# G22V2.net
KiCad netlist of a schematic drawn in EAGLE
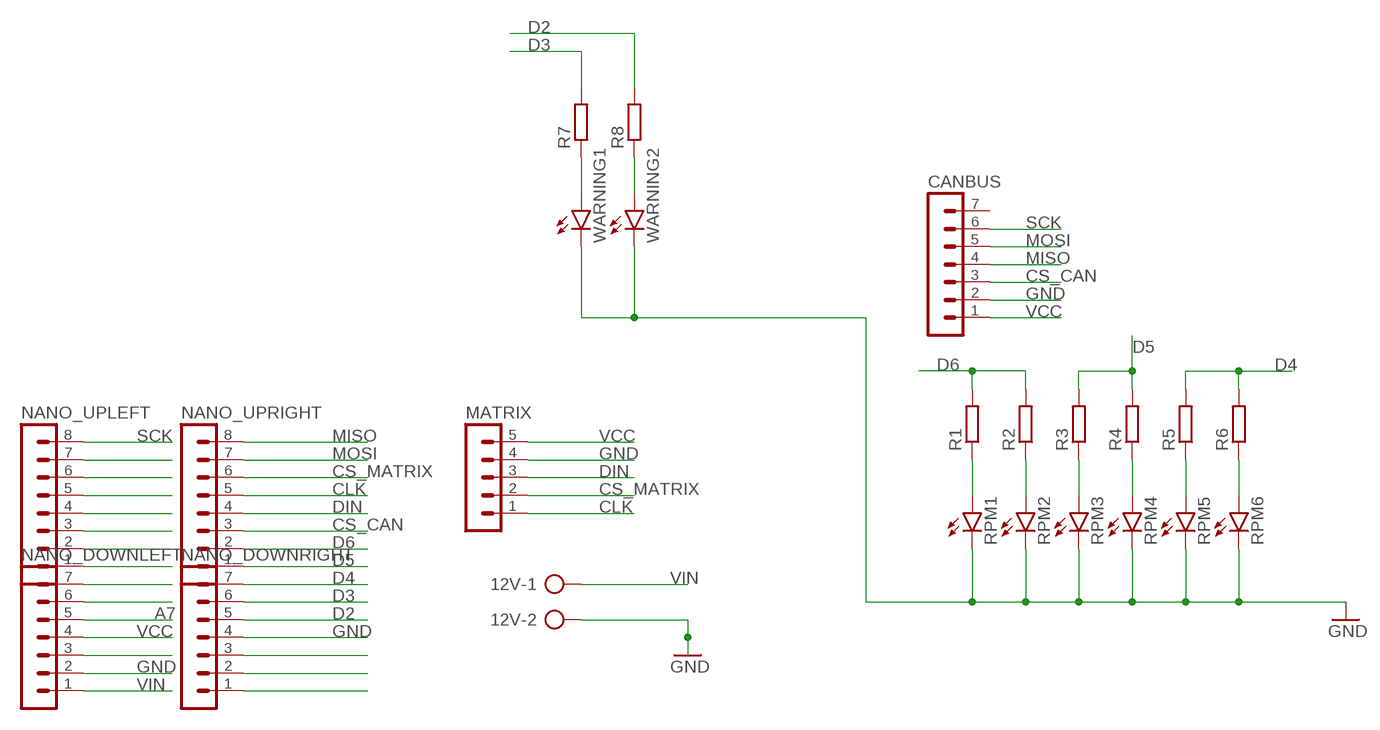
[diagram p0: schematic, sheet 1]

(export (version "E")
  (design (tool "Eeschema 10.0.6"))
  (components
    (comp (ref "12V")
      (value "AK500/2-H")
      (footprint "eagle-import:AK500_2-H")
      (libsource (lib "eagle-import") (part "AK500/2-H"))
    )
    (comp (ref "CANBUS")
      (value "MA07-1")
      (footprint "eagle-import:MA07-1")
      (libsource (lib "eagle-import") (part "MA07-1"))
    )
    (comp (ref "MATRIX")
      (value "MA05-1")
      (footprint "eagle-import:MA05-1")
      (libsource (lib "eagle-import") (part "MA05-1"))
    )
    (comp (ref "NANO_DOWNLEFT")
      (value "MA07-1")
      (footprint "eagle-import:MA07-1")
      (libsource (lib "eagle-import") (part "MA07-1"))
    )
    (comp (ref "NANO_DOWNRIGHT")
      (value "MA07-1")
      (footprint "eagle-import:MA07-1")
      (libsource (lib "eagle-import") (part "MA07-1"))
    )
    (comp (ref "NANO_UPLEFT")
      (value "MA08-1")
      (footprint "eagle-import:MA08-1")
      (libsource (lib "eagle-import") (part "MA08-1"))
    )
    (comp (ref "NANO_UPRIGHT")
      (value "MA08-1")
      (footprint "eagle-import:MA08-1")
      (libsource (lib "eagle-import") (part "MA08-1"))
    )
    (comp (ref "R1")
      (value "R-EU_0204/7")
      (footprint "eagle-import:0204_7")
      (libsource (lib "eagle-import") (part "R-EU_0204/7"))
    )
    (comp (ref "R2")
      (value "R-EU_0204/7")
      (footprint "eagle-import:0204_7")
      (libsource (lib "eagle-import") (part "R-EU_0204/7"))
    )
    (comp (ref "R3")
      (value "R-EU_0204/7")
      (footprint "eagle-import:0204_7")
      (libsource (lib "eagle-import") (part "R-EU_0204/7"))
    )
    (comp (ref "R4")
      (value "R-EU_0204/7")
      (footprint "eagle-import:0204_7")
      (libsource (lib "eagle-import") (part "R-EU_0204/7"))
    )
    (comp (ref "R5")
      (value "R-EU_0204/7")
      (footprint "eagle-import:0204_7")
      (libsource (lib "eagle-import") (part "R-EU_0204/7"))
    )
    (comp (ref "R6")
      (value "R-EU_0204/7")
      (footprint "eagle-import:0204_7")
      (libsource (lib "eagle-import") (part "R-EU_0204/7"))
    )
    (comp (ref "R7")
      (value "R-EU_0204/7")
      (footprint "eagle-import:0204_7")
      (libsource (lib "eagle-import") (part "R-EU_0204/7"))
    )
    (comp (ref "R8")
      (value "R-EU_0204/7")
      (footprint "eagle-import:0204_7")
      (libsource (lib "eagle-import") (part "R-EU_0204/7"))
    )
    (comp (ref "RPM1")
      (value "LED5MM")
      (footprint "eagle-import:LED5MM")
      (libsource (lib "eagle-import") (part "LED5MM"))
    )
    (comp (ref "RPM2")
      (value "LED5MM")
      (footprint "eagle-import:LED5MM")
      (libsource (lib "eagle-import") (part "LED5MM"))
    )
    (comp (ref "RPM3")
      (value "LED5MM")
      (footprint "eagle-import:LED5MM")
      (libsource (lib "eagle-import") (part "LED5MM"))
    )
    (comp (ref "RPM4")
      (value "LED5MM")
      (footprint "eagle-import:LED5MM")
      (libsource (lib "eagle-import") (part "LED5MM"))
    )
    (comp (ref "RPM5")
      (value "LED5MM")
      (footprint "eagle-import:LED5MM")
      (libsource (lib "eagle-import") (part "LED5MM"))
    )
    (comp (ref "RPM6")
      (value "LED5MM")
      (footprint "eagle-import:LED5MM")
      (libsource (lib "eagle-import") (part "LED5MM"))
    )
    (comp (ref "WARNING1")
      (value "LED5MM")
      (footprint "eagle-import:LED5MM")
      (libsource (lib "eagle-import") (part "LED5MM"))
    )
    (comp (ref "WARNING2")
      (value "LED5MM")
      (footprint "eagle-import:LED5MM")
      (libsource (lib "eagle-import") (part "LED5MM"))
    )
  )
  (nets
    (net (code "1") (name "/A7") (class "Default")
      (node (ref "NANO_DOWNLEFT") (pin "5") (pinfunction "5_5") (pintype "passive"))
    )
    (net (code "2") (name "/CLK") (class "Default")
      (node (ref "MATRIX") (pin "1") (pinfunction "1_1") (pintype "passive"))
      (node (ref "NANO_UPRIGHT") (pin "5") (pinfunction "5_5") (pintype "passive"))
    )
    (net (code "3") (name "/CS_CAN") (class "Default")
      (node (ref "CANBUS") (pin "3") (pinfunction "3_3") (pintype "passive"))
      (node (ref "NANO_UPRIGHT") (pin "3") (pinfunction "3_3") (pintype "passive"))
    )
    (net (code "4") (name "/CS_MATRIX") (class "Default")
      (node (ref "MATRIX") (pin "2") (pinfunction "2_2") (pintype "passive"))
      (node (ref "NANO_UPRIGHT") (pin "6") (pinfunction "6_6") (pintype "passive"))
    )
    (net (code "5") (name "/D2") (class "Default")
      (node (ref "NANO_DOWNRIGHT") (pin "5") (pinfunction "5_5") (pintype "passive"))
      (node (ref "R8") (pin "2") (pinfunction "2_2") (pintype "passive"))
    )
    (net (code "6") (name "/D3") (class "Default")
      (node (ref "NANO_DOWNRIGHT") (pin "6") (pinfunction "6_6") (pintype "passive"))
      (node (ref "R7") (pin "2") (pinfunction "2_2") (pintype "passive"))
    )
    (net (code "7") (name "/D4") (class "Default")
      (node (ref "NANO_DOWNRIGHT") (pin "7") (pinfunction "7_7") (pintype "passive"))
      (node (ref "R5") (pin "2") (pinfunction "2_2") (pintype "passive"))
      (node (ref "R6") (pin "2") (pinfunction "2_2") (pintype "passive"))
    )
    (net (code "8") (name "/D5") (class "Default")
      (node (ref "NANO_UPRIGHT") (pin "1") (pinfunction "1_1") (pintype "passive"))
      (node (ref "R3") (pin "2") (pinfunction "2_2") (pintype "passive"))
      (node (ref "R4") (pin "2") (pinfunction "2_2") (pintype "passive"))
    )
    (net (code "9") (name "/D6") (class "Default")
      (node (ref "NANO_UPRIGHT") (pin "2") (pinfunction "2_2") (pintype "passive"))
      (node (ref "R1") (pin "2") (pinfunction "2_2") (pintype "passive"))
      (node (ref "R2") (pin "2") (pinfunction "2_2") (pintype "passive"))
    )
    (net (code "10") (name "/DIN") (class "Default")
      (node (ref "MATRIX") (pin "3") (pinfunction "3_3") (pintype "passive"))
      (node (ref "NANO_UPRIGHT") (pin "4") (pinfunction "4_4") (pintype "passive"))
    )
    (net (code "11") (name "/MISO") (class "Default")
      (node (ref "CANBUS") (pin "4") (pinfunction "4_4") (pintype "passive"))
      (node (ref "NANO_UPRIGHT") (pin "8") (pinfunction "8_8") (pintype "passive"))
    )
    (net (code "12") (name "/MOSI") (class "Default")
      (node (ref "CANBUS") (pin "5") (pinfunction "5_5") (pintype "passive"))
      (node (ref "NANO_UPRIGHT") (pin "7") (pinfunction "7_7") (pintype "passive"))
    )
    (net (code "13") (name "/SCK") (class "Default")
      (node (ref "CANBUS") (pin "6") (pinfunction "6_6") (pintype "passive"))
      (node (ref "NANO_UPLEFT") (pin "8") (pinfunction "8_8") (pintype "passive"))
    )
    (net (code "14") (name "/VCC") (class "Default")
      (node (ref "CANBUS") (pin "1") (pinfunction "1_1") (pintype "passive"))
      (node (ref "MATRIX") (pin "5") (pinfunction "5_5") (pintype "passive"))
      (node (ref "NANO_DOWNLEFT") (pin "4") (pinfunction "4_4") (pintype "passive"))
    )
    (net (code "15") (name "/VIN") (class "Default")
      (node (ref "12V") (pin "1") (pinfunction "KL_1") (pintype "passive"))
      (node (ref "NANO_DOWNLEFT") (pin "1") (pinfunction "1_1") (pintype "passive"))
    )
    (net (code "16") (name "GND") (class "Default")
      (node (ref "12V") (pin "2") (pinfunction "KL_2") (pintype "passive"))
      (node (ref "CANBUS") (pin "2") (pinfunction "2_2") (pintype "passive"))
      (node (ref "MATRIX") (pin "4") (pinfunction "4_4") (pintype "passive"))
      (node (ref "NANO_DOWNLEFT") (pin "2") (pinfunction "2_2") (pintype "passive"))
      (node (ref "NANO_DOWNRIGHT") (pin "4") (pinfunction "4_4") (pintype "passive"))
      (node (ref "RPM1") (pin "K") (pinfunction "C_K") (pintype "passive"))
      (node (ref "RPM2") (pin "K") (pinfunction "C_K") (pintype "passive"))
      (node (ref "RPM3") (pin "K") (pinfunction "C_K") (pintype "passive"))
      (node (ref "RPM4") (pin "K") (pinfunction "C_K") (pintype "passive"))
      (node (ref "RPM5") (pin "K") (pinfunction "C_K") (pintype "passive"))
      (node (ref "RPM6") (pin "K") (pinfunction "C_K") (pintype "passive"))
      (node (ref "WARNING1") (pin "K") (pinfunction "C_K") (pintype "passive"))
      (node (ref "WARNING2") (pin "K") (pinfunction "C_K") (pintype "passive"))
    )
    (net (code "17") (name "Net-(R1-Pad1)") (class "Default")
      (node (ref "R1") (pin "1") (pinfunction "1_1") (pintype "passive"))
      (node (ref "RPM1") (pin "A") (pinfunction "A_A") (pintype "passive"))
    )
    (net (code "18") (name "Net-(R2-Pad1)") (class "Default")
      (node (ref "R2") (pin "1") (pinfunction "1_1") (pintype "passive"))
      (node (ref "RPM2") (pin "A") (pinfunction "A_A") (pintype "passive"))
    )
    (net (code "19") (name "Net-(R3-Pad1)") (class "Default")
      (node (ref "R3") (pin "1") (pinfunction "1_1") (pintype "passive"))
      (node (ref "RPM3") (pin "A") (pinfunction "A_A") (pintype "passive"))
    )
    (net (code "20") (name "Net-(R4-Pad1)") (class "Default")
      (node (ref "R4") (pin "1") (pinfunction "1_1") (pintype "passive"))
      (node (ref "RPM4") (pin "A") (pinfunction "A_A") (pintype "passive"))
    )
    (net (code "21") (name "Net-(R5-Pad1)") (class "Default")
      (node (ref "R5") (pin "1") (pinfunction "1_1") (pintype "passive"))
      (node (ref "RPM5") (pin "A") (pinfunction "A_A") (pintype "passive"))
    )
    (net (code "22") (name "Net-(R6-Pad1)") (class "Default")
      (node (ref "R6") (pin "1") (pinfunction "1_1") (pintype "passive"))
      (node (ref "RPM6") (pin "A") (pinfunction "A_A") (pintype "passive"))
    )
    (net (code "23") (name "Net-(R7-Pad1)") (class "Default")
      (node (ref "R7") (pin "1") (pinfunction "1_1") (pintype "passive"))
      (node (ref "WARNING1") (pin "A") (pinfunction "A_A") (pintype "passive"))
    )
    (net (code "24") (name "Net-(R8-Pad1)") (class "Default")
      (node (ref "R8") (pin "1") (pinfunction "1_1") (pintype "passive"))
      (node (ref "WARNING2") (pin "A") (pinfunction "A_A") (pintype "passive"))
    )
    (net (code "25") (name "unconnected-(CANBUS-Pad7)") (class "Default")
      (node (ref "CANBUS") (pin "7") (pinfunction "7_7") (pintype "passive"))
    )
    (net (code "26") (name "unconnected-(NANO_DOWNLEFT-Pad3)") (class "Default")
      (node (ref "NANO_DOWNLEFT") (pin "3") (pinfunction "3_3") (pintype "passive"))
    )
    (net (code "27") (name "unconnected-(NANO_DOWNLEFT-Pad6)") (class "Default")
      (node (ref "NANO_DOWNLEFT") (pin "6") (pinfunction "6_6") (pintype "passive"))
    )
    (net (code "28") (name "unconnected-(NANO_DOWNLEFT-Pad7)") (class "Default")
      (node (ref "NANO_DOWNLEFT") (pin "7") (pinfunction "7_7") (pintype "passive"))
    )
    (net (code "29") (name "unconnected-(NANO_DOWNRIGHT-Pad1)") (class "Default")
      (node (ref "NANO_DOWNRIGHT") (pin "1") (pinfunction "1_1") (pintype "passive"))
    )
    (net (code "30") (name "unconnected-(NANO_DOWNRIGHT-Pad2)") (class "Default")
      (node (ref "NANO_DOWNRIGHT") (pin "2") (pinfunction "2_2") (pintype "passive"))
    )
    (net (code "31") (name "unconnected-(NANO_DOWNRIGHT-Pad3)") (class "Default")
      (node (ref "NANO_DOWNRIGHT") (pin "3") (pinfunction "3_3") (pintype "passive"))
    )
    (net (code "32") (name "unconnected-(NANO_UPLEFT-Pad1)") (class "Default")
      (node (ref "NANO_UPLEFT") (pin "1") (pinfunction "1_1") (pintype "passive"))
    )
    (net (code "33") (name "unconnected-(NANO_UPLEFT-Pad2)") (class "Default")
      (node (ref "NANO_UPLEFT") (pin "2") (pinfunction "2_2") (pintype "passive"))
    )
    (net (code "34") (name "unconnected-(NANO_UPLEFT-Pad3)") (class "Default")
      (node (ref "NANO_UPLEFT") (pin "3") (pinfunction "3_3") (pintype "passive"))
    )
    (net (code "35") (name "unconnected-(NANO_UPLEFT-Pad4)") (class "Default")
      (node (ref "NANO_UPLEFT") (pin "4") (pinfunction "4_4") (pintype "passive"))
    )
    (net (code "36") (name "unconnected-(NANO_UPLEFT-Pad5)") (class "Default")
      (node (ref "NANO_UPLEFT") (pin "5") (pinfunction "5_5") (pintype "passive"))
    )
    (net (code "37") (name "unconnected-(NANO_UPLEFT-Pad6)") (class "Default")
      (node (ref "NANO_UPLEFT") (pin "6") (pinfunction "6_6") (pintype "passive"))
    )
    (net (code "38") (name "unconnected-(NANO_UPLEFT-Pad7)") (class "Default")
      (node (ref "NANO_UPLEFT") (pin "7") (pinfunction "7_7") (pintype "passive"))
    )
  )
)
